# ws2803.net
KiCad netlist of a schematic drawn in EAGLE
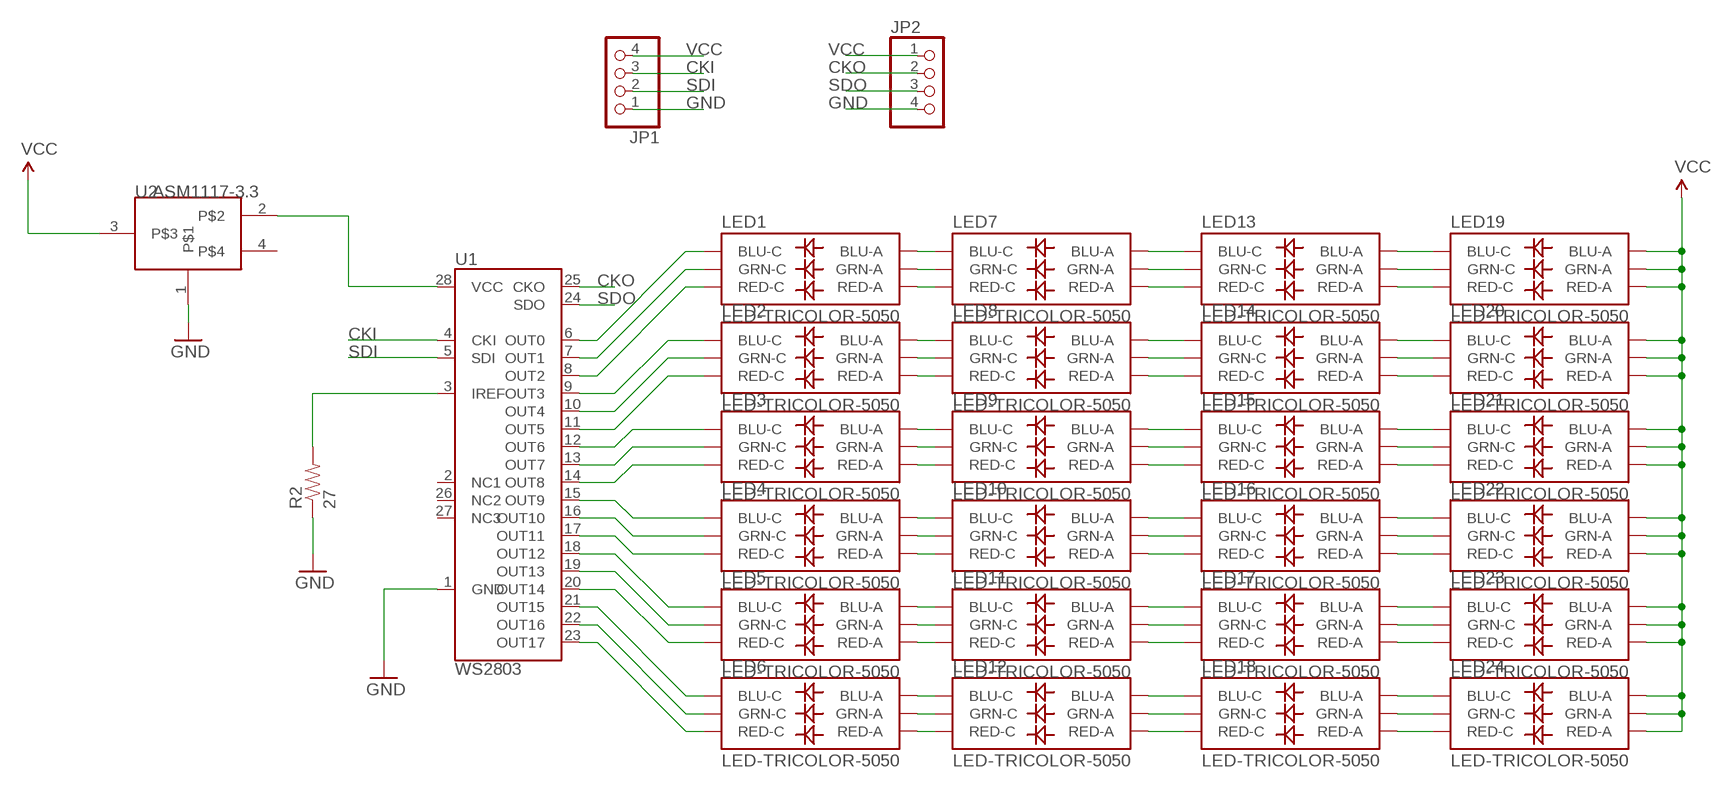
[diagram p0: schematic, sheet 1]

(export (version "E")
  (design (tool "Eeschema 10.0.6"))
  (components
    (comp (ref "JP1")
      (value "PINHD-1X4")
      (footprint "eagle-import:1X04")
      (libsource (lib "eagle-import") (part "PINHD-1X4"))
    )
    (comp (ref "JP2")
      (value "PINHD-1X4")
      (footprint "eagle-import:1X04")
      (libsource (lib "eagle-import") (part "PINHD-1X4"))
    )
    (comp (ref "LED1")
      (value "LED-TRICOLOR-5050")
      (footprint "eagle-import:LED-TRICOLOR-5050")
      (libsource (lib "eagle-import") (part "LED-TRICOLOR-5050"))
    )
    (comp (ref "LED2")
      (value "LED-TRICOLOR-5050")
      (footprint "eagle-import:LED-TRICOLOR-5050")
      (libsource (lib "eagle-import") (part "LED-TRICOLOR-5050"))
    )
    (comp (ref "LED3")
      (value "LED-TRICOLOR-5050")
      (footprint "eagle-import:LED-TRICOLOR-5050")
      (libsource (lib "eagle-import") (part "LED-TRICOLOR-5050"))
    )
    (comp (ref "LED4")
      (value "LED-TRICOLOR-5050")
      (footprint "eagle-import:LED-TRICOLOR-5050")
      (libsource (lib "eagle-import") (part "LED-TRICOLOR-5050"))
    )
    (comp (ref "LED5")
      (value "LED-TRICOLOR-5050")
      (footprint "eagle-import:LED-TRICOLOR-5050")
      (libsource (lib "eagle-import") (part "LED-TRICOLOR-5050"))
    )
    (comp (ref "LED6")
      (value "LED-TRICOLOR-5050")
      (footprint "eagle-import:LED-TRICOLOR-5050")
      (libsource (lib "eagle-import") (part "LED-TRICOLOR-5050"))
    )
    (comp (ref "LED7")
      (value "LED-TRICOLOR-5050")
      (footprint "eagle-import:LED-TRICOLOR-5050")
      (libsource (lib "eagle-import") (part "LED-TRICOLOR-5050"))
    )
    (comp (ref "LED8")
      (value "LED-TRICOLOR-5050")
      (footprint "eagle-import:LED-TRICOLOR-5050")
      (libsource (lib "eagle-import") (part "LED-TRICOLOR-5050"))
    )
    (comp (ref "LED9")
      (value "LED-TRICOLOR-5050")
      (footprint "eagle-import:LED-TRICOLOR-5050")
      (libsource (lib "eagle-import") (part "LED-TRICOLOR-5050"))
    )
    (comp (ref "LED10")
      (value "LED-TRICOLOR-5050")
      (footprint "eagle-import:LED-TRICOLOR-5050")
      (libsource (lib "eagle-import") (part "LED-TRICOLOR-5050"))
    )
    (comp (ref "LED11")
      (value "LED-TRICOLOR-5050")
      (footprint "eagle-import:LED-TRICOLOR-5050")
      (libsource (lib "eagle-import") (part "LED-TRICOLOR-5050"))
    )
    (comp (ref "LED12")
      (value "LED-TRICOLOR-5050")
      (footprint "eagle-import:LED-TRICOLOR-5050")
      (libsource (lib "eagle-import") (part "LED-TRICOLOR-5050"))
    )
    (comp (ref "LED13")
      (value "LED-TRICOLOR-5050")
      (footprint "eagle-import:LED-TRICOLOR-5050")
      (libsource (lib "eagle-import") (part "LED-TRICOLOR-5050"))
    )
    (comp (ref "LED14")
      (value "LED-TRICOLOR-5050")
      (footprint "eagle-import:LED-TRICOLOR-5050")
      (libsource (lib "eagle-import") (part "LED-TRICOLOR-5050"))
    )
    (comp (ref "LED15")
      (value "LED-TRICOLOR-5050")
      (footprint "eagle-import:LED-TRICOLOR-5050")
      (libsource (lib "eagle-import") (part "LED-TRICOLOR-5050"))
    )
    (comp (ref "LED16")
      (value "LED-TRICOLOR-5050")
      (footprint "eagle-import:LED-TRICOLOR-5050")
      (libsource (lib "eagle-import") (part "LED-TRICOLOR-5050"))
    )
    (comp (ref "LED17")
      (value "LED-TRICOLOR-5050")
      (footprint "eagle-import:LED-TRICOLOR-5050")
      (libsource (lib "eagle-import") (part "LED-TRICOLOR-5050"))
    )
    (comp (ref "LED18")
      (value "LED-TRICOLOR-5050")
      (footprint "eagle-import:LED-TRICOLOR-5050")
      (libsource (lib "eagle-import") (part "LED-TRICOLOR-5050"))
    )
    (comp (ref "LED19")
      (value "LED-TRICOLOR-5050")
      (footprint "eagle-import:LED-TRICOLOR-5050")
      (libsource (lib "eagle-import") (part "LED-TRICOLOR-5050"))
    )
    (comp (ref "LED20")
      (value "LED-TRICOLOR-5050")
      (footprint "eagle-import:LED-TRICOLOR-5050")
      (libsource (lib "eagle-import") (part "LED-TRICOLOR-5050"))
    )
    (comp (ref "LED21")
      (value "LED-TRICOLOR-5050")
      (footprint "eagle-import:LED-TRICOLOR-5050")
      (libsource (lib "eagle-import") (part "LED-TRICOLOR-5050"))
    )
    (comp (ref "LED22")
      (value "LED-TRICOLOR-5050")
      (footprint "eagle-import:LED-TRICOLOR-5050")
      (libsource (lib "eagle-import") (part "LED-TRICOLOR-5050"))
    )
    (comp (ref "LED23")
      (value "LED-TRICOLOR-5050")
      (footprint "eagle-import:LED-TRICOLOR-5050")
      (libsource (lib "eagle-import") (part "LED-TRICOLOR-5050"))
    )
    (comp (ref "LED24")
      (value "LED-TRICOLOR-5050")
      (footprint "eagle-import:LED-TRICOLOR-5050")
      (libsource (lib "eagle-import") (part "LED-TRICOLOR-5050"))
    )
    (comp (ref "R2")
      (value "27")
      (footprint "eagle-import:0603-RES")
      (libsource (lib "eagle-import") (part "RESISTOR0603-RES"))
    )
    (comp (ref "U1")
      (value "WS2803")
      (footprint "eagle-import:SOP-28")
      (libsource (lib "eagle-import") (part "WS2803"))
    )
    (comp (ref "U2")
      (value "ASM1117-3.3")
      (footprint "eagle-import:SOT223")
      (libsource (lib "eagle-import") (part "ASM1117-3.3"))
    )
  )
  (nets
    (net (code "1") (name "/CKI") (class "Default")
      (node (ref "JP1") (pin "3") (pinfunction "3_3") (pintype "passive"))
      (node (ref "U1") (pin "4") (pinfunction "CKI_4") (pintype "bidirectional"))
    )
    (net (code "2") (name "/CKO") (class "Default")
      (node (ref "JP2") (pin "2") (pinfunction "2_2") (pintype "passive"))
      (node (ref "U1") (pin "25") (pinfunction "CKO_25") (pintype "bidirectional"))
    )
    (net (code "3") (name "/SDI") (class "Default")
      (node (ref "JP1") (pin "2") (pinfunction "2_2") (pintype "passive"))
      (node (ref "U1") (pin "5") (pinfunction "SDI_5") (pintype "bidirectional"))
    )
    (net (code "4") (name "/SDO") (class "Default")
      (node (ref "JP2") (pin "3") (pinfunction "3_3") (pintype "passive"))
      (node (ref "U1") (pin "24") (pinfunction "SDO_24") (pintype "bidirectional"))
    )
    (net (code "5") (name "GND") (class "Default")
      (node (ref "JP1") (pin "1") (pinfunction "1_1") (pintype "passive"))
      (node (ref "JP2") (pin "4") (pinfunction "4_4") (pintype "passive"))
      (node (ref "R2") (pin "1") (pinfunction "1_1") (pintype "passive"))
      (node (ref "U1") (pin "1") (pinfunction "GND_1") (pintype "bidirectional"))
      (node (ref "U2") (pin "1") (pinfunction "P$1_1") (pintype "bidirectional"))
    )
    (net (code "6") (name "Net-(LED1-BLU-A)") (class "Default")
      (node (ref "LED1") (pin "3") (pinfunction "BLU-A_3") (pintype "bidirectional"))
      (node (ref "LED7") (pin "4") (pinfunction "BLU-C_4") (pintype "bidirectional"))
    )
    (net (code "7") (name "Net-(LED1-BLU-C)") (class "Default")
      (node (ref "LED1") (pin "4") (pinfunction "BLU-C_4") (pintype "bidirectional"))
      (node (ref "U1") (pin "6") (pinfunction "OUT0_6") (pintype "bidirectional"))
    )
    (net (code "8") (name "Net-(LED1-GRN-A)") (class "Default")
      (node (ref "LED1") (pin "1") (pinfunction "GRN-A_1") (pintype "bidirectional"))
      (node (ref "LED7") (pin "6") (pinfunction "GRN-C_6") (pintype "bidirectional"))
    )
    (net (code "9") (name "Net-(LED1-GRN-C)") (class "Default")
      (node (ref "LED1") (pin "6") (pinfunction "GRN-C_6") (pintype "bidirectional"))
      (node (ref "U1") (pin "7") (pinfunction "OUT1_7") (pintype "bidirectional"))
    )
    (net (code "10") (name "Net-(LED1-RED-A)") (class "Default")
      (node (ref "LED1") (pin "2") (pinfunction "RED-A_2") (pintype "bidirectional"))
      (node (ref "LED7") (pin "5") (pinfunction "RED-C_5") (pintype "bidirectional"))
    )
    (net (code "11") (name "Net-(LED1-RED-C)") (class "Default")
      (node (ref "LED1") (pin "5") (pinfunction "RED-C_5") (pintype "bidirectional"))
      (node (ref "U1") (pin "8") (pinfunction "OUT2_8") (pintype "bidirectional"))
    )
    (net (code "12") (name "Net-(LED2-BLU-A)") (class "Default")
      (node (ref "LED2") (pin "3") (pinfunction "BLU-A_3") (pintype "bidirectional"))
      (node (ref "LED8") (pin "4") (pinfunction "BLU-C_4") (pintype "bidirectional"))
    )
    (net (code "13") (name "Net-(LED2-BLU-C)") (class "Default")
      (node (ref "LED2") (pin "4") (pinfunction "BLU-C_4") (pintype "bidirectional"))
      (node (ref "U1") (pin "9") (pinfunction "OUT3_9") (pintype "bidirectional"))
    )
    (net (code "14") (name "Net-(LED2-GRN-A)") (class "Default")
      (node (ref "LED2") (pin "1") (pinfunction "GRN-A_1") (pintype "bidirectional"))
      (node (ref "LED8") (pin "6") (pinfunction "GRN-C_6") (pintype "bidirectional"))
    )
    (net (code "15") (name "Net-(LED2-GRN-C)") (class "Default")
      (node (ref "LED2") (pin "6") (pinfunction "GRN-C_6") (pintype "bidirectional"))
      (node (ref "U1") (pin "10") (pinfunction "OUT4_10") (pintype "bidirectional"))
    )
    (net (code "16") (name "Net-(LED2-RED-A)") (class "Default")
      (node (ref "LED2") (pin "2") (pinfunction "RED-A_2") (pintype "bidirectional"))
      (node (ref "LED8") (pin "5") (pinfunction "RED-C_5") (pintype "bidirectional"))
    )
    (net (code "17") (name "Net-(LED2-RED-C)") (class "Default")
      (node (ref "LED2") (pin "5") (pinfunction "RED-C_5") (pintype "bidirectional"))
      (node (ref "U1") (pin "11") (pinfunction "OUT5_11") (pintype "bidirectional"))
    )
    (net (code "18") (name "Net-(LED3-BLU-A)") (class "Default")
      (node (ref "LED3") (pin "3") (pinfunction "BLU-A_3") (pintype "bidirectional"))
      (node (ref "LED9") (pin "4") (pinfunction "BLU-C_4") (pintype "bidirectional"))
    )
    (net (code "19") (name "Net-(LED3-BLU-C)") (class "Default")
      (node (ref "LED3") (pin "4") (pinfunction "BLU-C_4") (pintype "bidirectional"))
      (node (ref "U1") (pin "12") (pinfunction "OUT6_12") (pintype "bidirectional"))
    )
    (net (code "20") (name "Net-(LED3-GRN-A)") (class "Default")
      (node (ref "LED3") (pin "1") (pinfunction "GRN-A_1") (pintype "bidirectional"))
      (node (ref "LED9") (pin "6") (pinfunction "GRN-C_6") (pintype "bidirectional"))
    )
    (net (code "21") (name "Net-(LED3-GRN-C)") (class "Default")
      (node (ref "LED3") (pin "6") (pinfunction "GRN-C_6") (pintype "bidirectional"))
      (node (ref "U1") (pin "13") (pinfunction "OUT7_13") (pintype "bidirectional"))
    )
    (net (code "22") (name "Net-(LED3-RED-A)") (class "Default")
      (node (ref "LED3") (pin "2") (pinfunction "RED-A_2") (pintype "bidirectional"))
      (node (ref "LED9") (pin "5") (pinfunction "RED-C_5") (pintype "bidirectional"))
    )
    (net (code "23") (name "Net-(LED3-RED-C)") (class "Default")
      (node (ref "LED3") (pin "5") (pinfunction "RED-C_5") (pintype "bidirectional"))
      (node (ref "U1") (pin "14") (pinfunction "OUT8_14") (pintype "bidirectional"))
    )
    (net (code "24") (name "Net-(LED4-BLU-C)") (class "Default")
      (node (ref "LED4") (pin "4") (pinfunction "BLU-C_4") (pintype "bidirectional"))
      (node (ref "U1") (pin "15") (pinfunction "OUT9_15") (pintype "bidirectional"))
    )
    (net (code "25") (name "Net-(LED4-GRN-C)") (class "Default")
      (node (ref "LED4") (pin "6") (pinfunction "GRN-C_6") (pintype "bidirectional"))
      (node (ref "U1") (pin "16") (pinfunction "OUT10_16") (pintype "bidirectional"))
    )
    (net (code "26") (name "Net-(LED4-RED-C)") (class "Default")
      (node (ref "LED4") (pin "5") (pinfunction "RED-C_5") (pintype "bidirectional"))
      (node (ref "U1") (pin "17") (pinfunction "OUT11_17") (pintype "bidirectional"))
    )
    (net (code "27") (name "Net-(LED5-BLU-C)") (class "Default")
      (node (ref "LED5") (pin "4") (pinfunction "BLU-C_4") (pintype "bidirectional"))
      (node (ref "U1") (pin "18") (pinfunction "OUT12_18") (pintype "bidirectional"))
    )
    (net (code "28") (name "Net-(LED5-GRN-C)") (class "Default")
      (node (ref "LED5") (pin "6") (pinfunction "GRN-C_6") (pintype "bidirectional"))
      (node (ref "U1") (pin "19") (pinfunction "OUT13_19") (pintype "bidirectional"))
    )
    (net (code "29") (name "Net-(LED5-RED-C)") (class "Default")
      (node (ref "LED5") (pin "5") (pinfunction "RED-C_5") (pintype "bidirectional"))
      (node (ref "U1") (pin "20") (pinfunction "OUT14_20") (pintype "bidirectional"))
    )
    (net (code "30") (name "Net-(LED6-BLU-C)") (class "Default")
      (node (ref "LED6") (pin "4") (pinfunction "BLU-C_4") (pintype "bidirectional"))
      (node (ref "U1") (pin "21") (pinfunction "OUT15_21") (pintype "bidirectional"))
    )
    (net (code "31") (name "Net-(LED6-GRN-C)") (class "Default")
      (node (ref "LED6") (pin "6") (pinfunction "GRN-C_6") (pintype "bidirectional"))
      (node (ref "U1") (pin "22") (pinfunction "OUT16_22") (pintype "bidirectional"))
    )
    (net (code "32") (name "Net-(LED6-RED-C)") (class "Default")
      (node (ref "LED6") (pin "5") (pinfunction "RED-C_5") (pintype "bidirectional"))
      (node (ref "U1") (pin "23") (pinfunction "OUT17_23") (pintype "bidirectional"))
    )
    (net (code "33") (name "Net-(LED10-BLU-A)") (class "Default")
      (node (ref "LED10") (pin "3") (pinfunction "BLU-A_3") (pintype "bidirectional"))
      (node (ref "LED16") (pin "4") (pinfunction "BLU-C_4") (pintype "bidirectional"))
    )
    (net (code "34") (name "Net-(LED10-BLU-C)") (class "Default")
      (node (ref "LED10") (pin "4") (pinfunction "BLU-C_4") (pintype "bidirectional"))
      (node (ref "LED4") (pin "3") (pinfunction "BLU-A_3") (pintype "bidirectional"))
    )
    (net (code "35") (name "Net-(LED10-GRN-A)") (class "Default")
      (node (ref "LED10") (pin "1") (pinfunction "GRN-A_1") (pintype "bidirectional"))
      (node (ref "LED16") (pin "6") (pinfunction "GRN-C_6") (pintype "bidirectional"))
    )
    (net (code "36") (name "Net-(LED10-GRN-C)") (class "Default")
      (node (ref "LED10") (pin "6") (pinfunction "GRN-C_6") (pintype "bidirectional"))
      (node (ref "LED4") (pin "1") (pinfunction "GRN-A_1") (pintype "bidirectional"))
    )
    (net (code "37") (name "Net-(LED10-RED-A)") (class "Default")
      (node (ref "LED10") (pin "2") (pinfunction "RED-A_2") (pintype "bidirectional"))
      (node (ref "LED16") (pin "5") (pinfunction "RED-C_5") (pintype "bidirectional"))
    )
    (net (code "38") (name "Net-(LED10-RED-C)") (class "Default")
      (node (ref "LED10") (pin "5") (pinfunction "RED-C_5") (pintype "bidirectional"))
      (node (ref "LED4") (pin "2") (pinfunction "RED-A_2") (pintype "bidirectional"))
    )
    (net (code "39") (name "Net-(LED11-BLU-A)") (class "Default")
      (node (ref "LED11") (pin "3") (pinfunction "BLU-A_3") (pintype "bidirectional"))
      (node (ref "LED17") (pin "4") (pinfunction "BLU-C_4") (pintype "bidirectional"))
    )
    (net (code "40") (name "Net-(LED11-BLU-C)") (class "Default")
      (node (ref "LED11") (pin "4") (pinfunction "BLU-C_4") (pintype "bidirectional"))
      (node (ref "LED5") (pin "3") (pinfunction "BLU-A_3") (pintype "bidirectional"))
    )
    (net (code "41") (name "Net-(LED11-GRN-A)") (class "Default")
      (node (ref "LED11") (pin "1") (pinfunction "GRN-A_1") (pintype "bidirectional"))
      (node (ref "LED17") (pin "6") (pinfunction "GRN-C_6") (pintype "bidirectional"))
    )
    (net (code "42") (name "Net-(LED11-GRN-C)") (class "Default")
      (node (ref "LED11") (pin "6") (pinfunction "GRN-C_6") (pintype "bidirectional"))
      (node (ref "LED5") (pin "1") (pinfunction "GRN-A_1") (pintype "bidirectional"))
    )
    (net (code "43") (name "Net-(LED11-RED-A)") (class "Default")
      (node (ref "LED11") (pin "2") (pinfunction "RED-A_2") (pintype "bidirectional"))
      (node (ref "LED17") (pin "5") (pinfunction "RED-C_5") (pintype "bidirectional"))
    )
    (net (code "44") (name "Net-(LED11-RED-C)") (class "Default")
      (node (ref "LED11") (pin "5") (pinfunction "RED-C_5") (pintype "bidirectional"))
      (node (ref "LED5") (pin "2") (pinfunction "RED-A_2") (pintype "bidirectional"))
    )
    (net (code "45") (name "Net-(LED12-BLU-A)") (class "Default")
      (node (ref "LED12") (pin "3") (pinfunction "BLU-A_3") (pintype "bidirectional"))
      (node (ref "LED18") (pin "4") (pinfunction "BLU-C_4") (pintype "bidirectional"))
    )
    (net (code "46") (name "Net-(LED12-BLU-C)") (class "Default")
      (node (ref "LED12") (pin "4") (pinfunction "BLU-C_4") (pintype "bidirectional"))
      (node (ref "LED6") (pin "3") (pinfunction "BLU-A_3") (pintype "bidirectional"))
    )
    (net (code "47") (name "Net-(LED12-GRN-A)") (class "Default")
      (node (ref "LED12") (pin "1") (pinfunction "GRN-A_1") (pintype "bidirectional"))
      (node (ref "LED18") (pin "6") (pinfunction "GRN-C_6") (pintype "bidirectional"))
    )
    (net (code "48") (name "Net-(LED12-GRN-C)") (class "Default")
      (node (ref "LED12") (pin "6") (pinfunction "GRN-C_6") (pintype "bidirectional"))
      (node (ref "LED6") (pin "1") (pinfunction "GRN-A_1") (pintype "bidirectional"))
    )
    (net (code "49") (name "Net-(LED12-RED-A)") (class "Default")
      (node (ref "LED12") (pin "2") (pinfunction "RED-A_2") (pintype "bidirectional"))
      (node (ref "LED18") (pin "5") (pinfunction "RED-C_5") (pintype "bidirectional"))
    )
    (net (code "50") (name "Net-(LED12-RED-C)") (class "Default")
      (node (ref "LED12") (pin "5") (pinfunction "RED-C_5") (pintype "bidirectional"))
      (node (ref "LED6") (pin "2") (pinfunction "RED-A_2") (pintype "bidirectional"))
    )
    (net (code "51") (name "Net-(LED13-BLU-A)") (class "Default")
      (node (ref "LED13") (pin "3") (pinfunction "BLU-A_3") (pintype "bidirectional"))
      (node (ref "LED19") (pin "4") (pinfunction "BLU-C_4") (pintype "bidirectional"))
    )
    (net (code "52") (name "Net-(LED13-BLU-C)") (class "Default")
      (node (ref "LED13") (pin "4") (pinfunction "BLU-C_4") (pintype "bidirectional"))
      (node (ref "LED7") (pin "3") (pinfunction "BLU-A_3") (pintype "bidirectional"))
    )
    (net (code "53") (name "Net-(LED13-GRN-A)") (class "Default")
      (node (ref "LED13") (pin "1") (pinfunction "GRN-A_1") (pintype "bidirectional"))
      (node (ref "LED19") (pin "6") (pinfunction "GRN-C_6") (pintype "bidirectional"))
    )
    (net (code "54") (name "Net-(LED13-GRN-C)") (class "Default")
      (node (ref "LED13") (pin "6") (pinfunction "GRN-C_6") (pintype "bidirectional"))
      (node (ref "LED7") (pin "1") (pinfunction "GRN-A_1") (pintype "bidirectional"))
    )
    (net (code "55") (name "Net-(LED13-RED-A)") (class "Default")
      (node (ref "LED13") (pin "2") (pinfunction "RED-A_2") (pintype "bidirectional"))
      (node (ref "LED19") (pin "5") (pinfunction "RED-C_5") (pintype "bidirectional"))
    )
    (net (code "56") (name "Net-(LED13-RED-C)") (class "Default")
      (node (ref "LED13") (pin "5") (pinfunction "RED-C_5") (pintype "bidirectional"))
      (node (ref "LED7") (pin "2") (pinfunction "RED-A_2") (pintype "bidirectional"))
    )
    (net (code "57") (name "Net-(LED14-BLU-A)") (class "Default")
      (node (ref "LED14") (pin "3") (pinfunction "BLU-A_3") (pintype "bidirectional"))
      (node (ref "LED20") (pin "4") (pinfunction "BLU-C_4") (pintype "bidirectional"))
    )
    (net (code "58") (name "Net-(LED14-BLU-C)") (class "Default")
      (node (ref "LED14") (pin "4") (pinfunction "BLU-C_4") (pintype "bidirectional"))
      (node (ref "LED8") (pin "3") (pinfunction "BLU-A_3") (pintype "bidirectional"))
    )
    (net (code "59") (name "Net-(LED14-GRN-A)") (class "Default")
      (node (ref "LED14") (pin "1") (pinfunction "GRN-A_1") (pintype "bidirectional"))
      (node (ref "LED20") (pin "6") (pinfunction "GRN-C_6") (pintype "bidirectional"))
    )
    (net (code "60") (name "Net-(LED14-GRN-C)") (class "Default")
      (node (ref "LED14") (pin "6") (pinfunction "GRN-C_6") (pintype "bidirectional"))
      (node (ref "LED8") (pin "1") (pinfunction "GRN-A_1") (pintype "bidirectional"))
    )
    (net (code "61") (name "Net-(LED14-RED-A)") (class "Default")
      (node (ref "LED14") (pin "2") (pinfunction "RED-A_2") (pintype "bidirectional"))
      (node (ref "LED20") (pin "5") (pinfunction "RED-C_5") (pintype "bidirectional"))
    )
    (net (code "62") (name "Net-(LED14-RED-C)") (class "Default")
      (node (ref "LED14") (pin "5") (pinfunction "RED-C_5") (pintype "bidirectional"))
      (node (ref "LED8") (pin "2") (pinfunction "RED-A_2") (pintype "bidirectional"))
    )
    (net (code "63") (name "Net-(LED15-BLU-A)") (class "Default")
      (node (ref "LED15") (pin "3") (pinfunction "BLU-A_3") (pintype "bidirectional"))
      (node (ref "LED21") (pin "4") (pinfunction "BLU-C_4") (pintype "bidirectional"))
    )
    (net (code "64") (name "Net-(LED15-BLU-C)") (class "Default")
      (node (ref "LED15") (pin "4") (pinfunction "BLU-C_4") (pintype "bidirectional"))
      (node (ref "LED9") (pin "3") (pinfunction "BLU-A_3") (pintype "bidirectional"))
    )
    (net (code "65") (name "Net-(LED15-GRN-A)") (class "Default")
      (node (ref "LED15") (pin "1") (pinfunction "GRN-A_1") (pintype "bidirectional"))
      (node (ref "LED21") (pin "6") (pinfunction "GRN-C_6") (pintype "bidirectional"))
    )
    (net (code "66") (name "Net-(LED15-GRN-C)") (class "Default")
      (node (ref "LED15") (pin "6") (pinfunction "GRN-C_6") (pintype "bidirectional"))
      (node (ref "LED9") (pin "1") (pinfunction "GRN-A_1") (pintype "bidirectional"))
    )
    (net (code "67") (name "Net-(LED15-RED-A)") (class "Default")
      (node (ref "LED15") (pin "2") (pinfunction "RED-A_2") (pintype "bidirectional"))
      (node (ref "LED21") (pin "5") (pinfunction "RED-C_5") (pintype "bidirectional"))
    )
    (net (code "68") (name "Net-(LED15-RED-C)") (class "Default")
      (node (ref "LED15") (pin "5") (pinfunction "RED-C_5") (pintype "bidirectional"))
      (node (ref "LED9") (pin "2") (pinfunction "RED-A_2") (pintype "bidirectional"))
    )
    (net (code "69") (name "Net-(LED16-BLU-A)") (class "Default")
      (node (ref "LED16") (pin "3") (pinfunction "BLU-A_3") (pintype "bidirectional"))
      (node (ref "LED22") (pin "4") (pinfunction "BLU-C_4") (pintype "bidirectional"))
    )
    (net (code "70") (name "Net-(LED16-GRN-A)") (class "Default")
      (node (ref "LED16") (pin "1") (pinfunction "GRN-A_1") (pintype "bidirectional"))
      (node (ref "LED22") (pin "6") (pinfunction "GRN-C_6") (pintype "bidirectional"))
    )
    (net (code "71") (name "Net-(LED16-RED-A)") (class "Default")
      (node (ref "LED16") (pin "2") (pinfunction "RED-A_2") (pintype "bidirectional"))
      (node (ref "LED22") (pin "5") (pinfunction "RED-C_5") (pintype "bidirectional"))
    )
    (net (code "72") (name "Net-(LED17-BLU-A)") (class "Default")
      (node (ref "LED17") (pin "3") (pinfunction "BLU-A_3") (pintype "bidirectional"))
      (node (ref "LED23") (pin "4") (pinfunction "BLU-C_4") (pintype "bidirectional"))
    )
    (net (code "73") (name "Net-(LED17-GRN-A)") (class "Default")
      (node (ref "LED17") (pin "1") (pinfunction "GRN-A_1") (pintype "bidirectional"))
      (node (ref "LED23") (pin "6") (pinfunction "GRN-C_6") (pintype "bidirectional"))
    )
    (net (code "74") (name "Net-(LED17-RED-A)") (class "Default")
      (node (ref "LED17") (pin "2") (pinfunction "RED-A_2") (pintype "bidirectional"))
      (node (ref "LED23") (pin "5") (pinfunction "RED-C_5") (pintype "bidirectional"))
    )
    (net (code "75") (name "Net-(LED18-BLU-A)") (class "Default")
      (node (ref "LED18") (pin "3") (pinfunction "BLU-A_3") (pintype "bidirectional"))
      (node (ref "LED24") (pin "4") (pinfunction "BLU-C_4") (pintype "bidirectional"))
    )
    (net (code "76") (name "Net-(LED18-GRN-A)") (class "Default")
      (node (ref "LED18") (pin "1") (pinfunction "GRN-A_1") (pintype "bidirectional"))
      (node (ref "LED24") (pin "6") (pinfunction "GRN-C_6") (pintype "bidirectional"))
    )
    (net (code "77") (name "Net-(LED18-RED-A)") (class "Default")
      (node (ref "LED18") (pin "2") (pinfunction "RED-A_2") (pintype "bidirectional"))
      (node (ref "LED24") (pin "5") (pinfunction "RED-C_5") (pintype "bidirectional"))
    )
    (net (code "78") (name "Net-(U1-IREF)") (class "Default")
      (node (ref "R2") (pin "2") (pinfunction "2_2") (pintype "passive"))
      (node (ref "U1") (pin "3") (pinfunction "IREF_3") (pintype "bidirectional"))
    )
    (net (code "79") (name "Net-(U1-VCC)") (class "Default")
      (node (ref "U1") (pin "28") (pinfunction "VCC_28") (pintype "bidirectional"))
      (node (ref "U2") (pin "2") (pinfunction "P$2_2") (pintype "bidirectional"))
    )
    (net (code "80") (name "VCC") (class "Default")
      (node (ref "JP1") (pin "4") (pinfunction "4_4") (pintype "passive"))
      (node (ref "JP2") (pin "1") (pinfunction "1_1") (pintype "passive"))
      (node (ref "LED19") (pin "1") (pinfunction "GRN-A_1") (pintype "bidirectional"))
      (node (ref "LED19") (pin "2") (pinfunction "RED-A_2") (pintype "bidirectional"))
      (node (ref "LED19") (pin "3") (pinfunction "BLU-A_3") (pintype "bidirectional"))
      (node (ref "LED20") (pin "1") (pinfunction "GRN-A_1") (pintype "bidirectional"))
      (node (ref "LED20") (pin "2") (pinfunction "RED-A_2") (pintype "bidirectional"))
      (node (ref "LED20") (pin "3") (pinfunction "BLU-A_3") (pintype "bidirectional"))
      (node (ref "LED21") (pin "1") (pinfunction "GRN-A_1") (pintype "bidirectional"))
      (node (ref "LED21") (pin "2") (pinfunction "RED-A_2") (pintype "bidirectional"))
      (node (ref "LED21") (pin "3") (pinfunction "BLU-A_3") (pintype "bidirectional"))
      (node (ref "LED22") (pin "1") (pinfunction "GRN-A_1") (pintype "bidirectional"))
      (node (ref "LED22") (pin "2") (pinfunction "RED-A_2") (pintype "bidirectional"))
      (node (ref "LED22") (pin "3") (pinfunction "BLU-A_3") (pintype "bidirectional"))
      (node (ref "LED23") (pin "1") (pinfunction "GRN-A_1") (pintype "bidirectional"))
      (node (ref "LED23") (pin "2") (pinfunction "RED-A_2") (pintype "bidirectional"))
      (node (ref "LED23") (pin "3") (pinfunction "BLU-A_3") (pintype "bidirectional"))
      (node (ref "LED24") (pin "1") (pinfunction "GRN-A_1") (pintype "bidirectional"))
      (node (ref "LED24") (pin "2") (pinfunction "RED-A_2") (pintype "bidirectional"))
      (node (ref "LED24") (pin "3") (pinfunction "BLU-A_3") (pintype "bidirectional"))
      (node (ref "U2") (pin "3") (pinfunction "P$3_3") (pintype "bidirectional"))
    )
    (net (code "81") (name "unconnected-(U1-NC1-Pad2)") (class "Default")
      (node (ref "U1") (pin "2") (pinfunction "NC1_2") (pintype "bidirectional"))
    )
    (net (code "82") (name "unconnected-(U1-NC2-Pad26)") (class "Default")
      (node (ref "U1") (pin "26") (pinfunction "NC2_26") (pintype "bidirectional"))
    )
    (net (code "83") (name "unconnected-(U1-NC3-Pad27)") (class "Default")
      (node (ref "U1") (pin "27") (pinfunction "NC3_27") (pintype "bidirectional"))
    )
    (net (code "84") (name "unconnected-(U2-P$4-Pad4)") (class "Default")
      (node (ref "U2") (pin "4") (pinfunction "P$4_4") (pintype "bidirectional"))
    )
  )
)
